# kbd.net
KiCad netlist of a schematic drawn in EAGLE
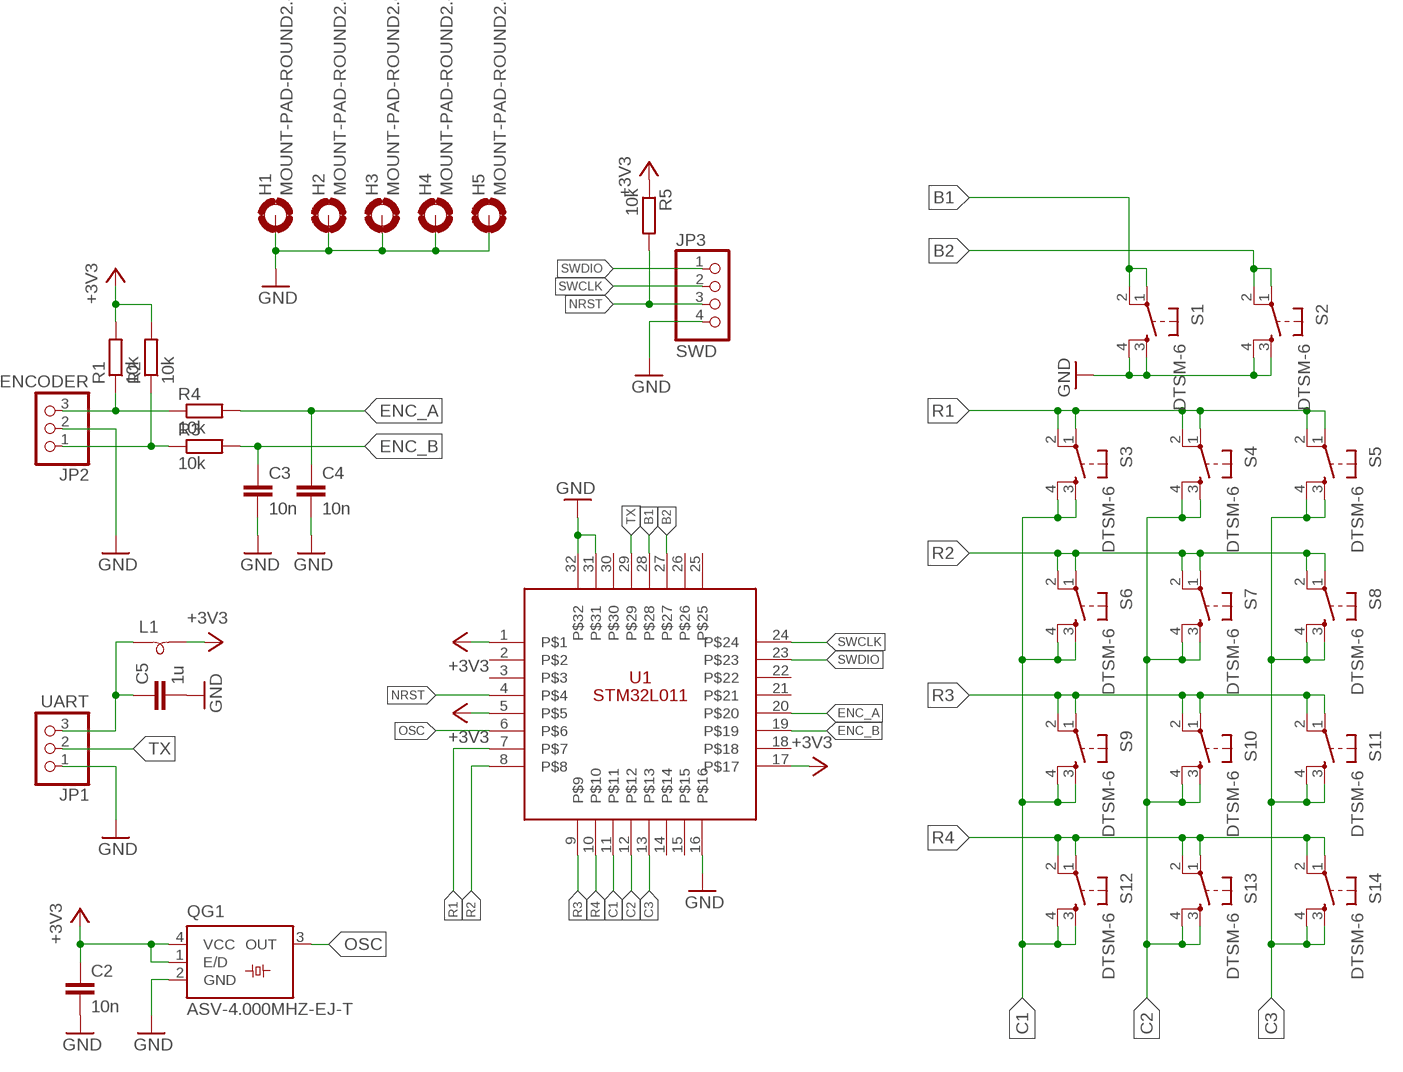
[diagram p0: schematic, sheet 1]

(export (version "E")
  (design (tool "Eeschema 10.0.6"))
  (components
    (comp (ref "C2")
      (value "10n")
      (footprint "eagle-import:C0805")
      (libsource (lib "eagle-import") (part "C-EUC0805"))
    )
    (comp (ref "C3")
      (value "10n")
      (footprint "eagle-import:C0805")
      (libsource (lib "eagle-import") (part "C-EUC0805"))
    )
    (comp (ref "C4")
      (value "10n")
      (footprint "eagle-import:C0805")
      (libsource (lib "eagle-import") (part "C-EUC0805"))
    )
    (comp (ref "C5")
      (value "1u")
      (footprint "eagle-import:C1206")
      (libsource (lib "eagle-import") (part "C-EUC1206"))
    )
    (comp (ref "H1")
      (value "MOUNT-PAD-ROUND2.8")
      (footprint "eagle-import:2,8-PAD")
      (libsource (lib "eagle-import") (part "MOUNT-PAD-ROUND2.8"))
    )
    (comp (ref "H2")
      (value "MOUNT-PAD-ROUND2.8")
      (footprint "eagle-import:2,8-PAD")
      (libsource (lib "eagle-import") (part "MOUNT-PAD-ROUND2.8"))
    )
    (comp (ref "H3")
      (value "MOUNT-PAD-ROUND2.8")
      (footprint "eagle-import:2,8-PAD")
      (libsource (lib "eagle-import") (part "MOUNT-PAD-ROUND2.8"))
    )
    (comp (ref "H4")
      (value "MOUNT-PAD-ROUND2.8")
      (footprint "eagle-import:2,8-PAD")
      (libsource (lib "eagle-import") (part "MOUNT-PAD-ROUND2.8"))
    )
    (comp (ref "H5")
      (value "MOUNT-PAD-ROUND2.8")
      (footprint "eagle-import:2,8-PAD")
      (libsource (lib "eagle-import") (part "MOUNT-PAD-ROUND2.8"))
    )
    (comp (ref "JP1")
      (value "UART")
      (footprint "eagle-import:1X03")
      (libsource (lib "eagle-import") (part "PINHD-1X3"))
    )
    (comp (ref "JP2")
      (value "ENCODER")
      (footprint "eagle-import:1X03")
      (libsource (lib "eagle-import") (part "PINHD-1X3"))
    )
    (comp (ref "JP3")
      (value "SWD")
      (footprint "eagle-import:1X04")
      (libsource (lib "eagle-import") (part "PINHD-1X4"))
    )
    (comp (ref "L1")
      (value "SM-B5")
      (footprint "eagle-import:SM-B5")
      (libsource (lib "eagle-import") (part "SM-B5"))
    )
    (comp (ref "QG1")
      (value "ASV-4.000MHZ-EJ-T")
      (footprint "eagle-import:SM77H")
      (libsource (lib "eagle-import") (part "SM77H"))
    )
    (comp (ref "R1")
      (value "10k")
      (footprint "eagle-import:R0805")
      (libsource (lib "eagle-import") (part "R-EU_R0805"))
    )
    (comp (ref "R2")
      (value "10k")
      (footprint "eagle-import:R0805")
      (libsource (lib "eagle-import") (part "R-EU_R0805"))
    )
    (comp (ref "R3")
      (value "10k")
      (footprint "eagle-import:R0805")
      (libsource (lib "eagle-import") (part "R-EU_R0805"))
    )
    (comp (ref "R4")
      (value "10k")
      (footprint "eagle-import:R0805")
      (libsource (lib "eagle-import") (part "R-EU_R0805"))
    )
    (comp (ref "R5")
      (value "10k")
      (footprint "eagle-import:R0805")
      (libsource (lib "eagle-import") (part "R-EU_R0805"))
    )
    (comp (ref "S1")
      (value "DTSM-6")
      (footprint "eagle-import:DTSM-6")
      (libsource (lib "eagle-import") (part "DTSM-6"))
    )
    (comp (ref "S2")
      (value "DTSM-6")
      (footprint "eagle-import:DTSM-6")
      (libsource (lib "eagle-import") (part "DTSM-6"))
    )
    (comp (ref "S3")
      (value "DTSM-6")
      (footprint "eagle-import:DTSM-6")
      (libsource (lib "eagle-import") (part "DTSM-6"))
    )
    (comp (ref "S4")
      (value "DTSM-6")
      (footprint "eagle-import:DTSM-6")
      (libsource (lib "eagle-import") (part "DTSM-6"))
    )
    (comp (ref "S5")
      (value "DTSM-6")
      (footprint "eagle-import:DTSM-6")
      (libsource (lib "eagle-import") (part "DTSM-6"))
    )
    (comp (ref "S6")
      (value "DTSM-6")
      (footprint "eagle-import:DTSM-6")
      (libsource (lib "eagle-import") (part "DTSM-6"))
    )
    (comp (ref "S7")
      (value "DTSM-6")
      (footprint "eagle-import:DTSM-6")
      (libsource (lib "eagle-import") (part "DTSM-6"))
    )
    (comp (ref "S8")
      (value "DTSM-6")
      (footprint "eagle-import:DTSM-6")
      (libsource (lib "eagle-import") (part "DTSM-6"))
    )
    (comp (ref "S9")
      (value "DTSM-6")
      (footprint "eagle-import:DTSM-6")
      (libsource (lib "eagle-import") (part "DTSM-6"))
    )
    (comp (ref "S10")
      (value "DTSM-6")
      (footprint "eagle-import:DTSM-6")
      (libsource (lib "eagle-import") (part "DTSM-6"))
    )
    (comp (ref "S11")
      (value "DTSM-6")
      (footprint "eagle-import:DTSM-6")
      (libsource (lib "eagle-import") (part "DTSM-6"))
    )
    (comp (ref "S12")
      (value "DTSM-6")
      (footprint "eagle-import:DTSM-6")
      (libsource (lib "eagle-import") (part "DTSM-6"))
    )
    (comp (ref "S13")
      (value "DTSM-6")
      (footprint "eagle-import:DTSM-6")
      (libsource (lib "eagle-import") (part "DTSM-6"))
    )
    (comp (ref "S14")
      (value "DTSM-6")
      (footprint "eagle-import:DTSM-6")
      (libsource (lib "eagle-import") (part "DTSM-6"))
    )
    (comp (ref "U1")
      (value "STM32L011")
      (footprint "eagle-import:LQFP32-7X7")
      (libsource (lib "eagle-import") (part "STM32L011"))
    )
  )
  (nets
    (net (code "1") (name "+3V3") (class "Default")
      (node (ref "C2") (pin "1") (pinfunction "1_1") (pintype "passive"))
      (node (ref "L1") (pin "2") (pinfunction "2_2") (pintype "passive"))
      (node (ref "QG1") (pin "1") (pinfunction "E/D_1") (pintype "input"))
      (node (ref "QG1") (pin "4") (pinfunction "VCC_4") (pintype "power_in"))
      (node (ref "R1") (pin "2") (pinfunction "2_2") (pintype "passive"))
      (node (ref "R2") (pin "2") (pinfunction "2_2") (pintype "passive"))
      (node (ref "R5") (pin "1") (pinfunction "1_1") (pintype "passive"))
      (node (ref "U1") (pin "1") (pinfunction "P$1_1") (pintype "bidirectional"))
      (node (ref "U1") (pin "17") (pinfunction "P$17_17") (pintype "bidirectional"))
      (node (ref "U1") (pin "5") (pinfunction "P$5_5") (pintype "bidirectional"))
    )
    (net (code "2") (name "B1") (class "Default")
      (node (ref "S1") (pin "1") (pinfunction "1_1") (pintype "passive"))
      (node (ref "S1") (pin "2") (pinfunction "2_2") (pintype "passive"))
      (node (ref "U1") (pin "28") (pinfunction "P$28_28") (pintype "bidirectional"))
    )
    (net (code "3") (name "B2") (class "Default")
      (node (ref "S2") (pin "1") (pinfunction "1_1") (pintype "passive"))
      (node (ref "S2") (pin "2") (pinfunction "2_2") (pintype "passive"))
      (node (ref "U1") (pin "27") (pinfunction "P$27_27") (pintype "bidirectional"))
    )
    (net (code "4") (name "C1") (class "Default")
      (node (ref "S12") (pin "3") (pinfunction "3_3") (pintype "passive"))
      (node (ref "S12") (pin "4") (pinfunction "4_4") (pintype "passive"))
      (node (ref "S3") (pin "3") (pinfunction "3_3") (pintype "passive"))
      (node (ref "S3") (pin "4") (pinfunction "4_4") (pintype "passive"))
      (node (ref "S6") (pin "3") (pinfunction "3_3") (pintype "passive"))
      (node (ref "S6") (pin "4") (pinfunction "4_4") (pintype "passive"))
      (node (ref "S9") (pin "3") (pinfunction "3_3") (pintype "passive"))
      (node (ref "S9") (pin "4") (pinfunction "4_4") (pintype "passive"))
      (node (ref "U1") (pin "11") (pinfunction "P$11_11") (pintype "bidirectional"))
    )
    (net (code "5") (name "C2") (class "Default")
      (node (ref "S10") (pin "3") (pinfunction "3_3") (pintype "passive"))
      (node (ref "S10") (pin "4") (pinfunction "4_4") (pintype "passive"))
      (node (ref "S13") (pin "3") (pinfunction "3_3") (pintype "passive"))
      (node (ref "S13") (pin "4") (pinfunction "4_4") (pintype "passive"))
      (node (ref "S4") (pin "3") (pinfunction "3_3") (pintype "passive"))
      (node (ref "S4") (pin "4") (pinfunction "4_4") (pintype "passive"))
      (node (ref "S7") (pin "3") (pinfunction "3_3") (pintype "passive"))
      (node (ref "S7") (pin "4") (pinfunction "4_4") (pintype "passive"))
      (node (ref "U1") (pin "12") (pinfunction "P$12_12") (pintype "bidirectional"))
    )
    (net (code "6") (name "C3") (class "Default")
      (node (ref "S11") (pin "3") (pinfunction "3_3") (pintype "passive"))
      (node (ref "S11") (pin "4") (pinfunction "4_4") (pintype "passive"))
      (node (ref "S14") (pin "3") (pinfunction "3_3") (pintype "passive"))
      (node (ref "S14") (pin "4") (pinfunction "4_4") (pintype "passive"))
      (node (ref "S5") (pin "3") (pinfunction "3_3") (pintype "passive"))
      (node (ref "S5") (pin "4") (pinfunction "4_4") (pintype "passive"))
      (node (ref "S8") (pin "3") (pinfunction "3_3") (pintype "passive"))
      (node (ref "S8") (pin "4") (pinfunction "4_4") (pintype "passive"))
      (node (ref "U1") (pin "13") (pinfunction "P$13_13") (pintype "bidirectional"))
    )
    (net (code "7") (name "ENC_A") (class "Default")
      (node (ref "C4") (pin "1") (pinfunction "1_1") (pintype "passive"))
      (node (ref "R4") (pin "2") (pinfunction "2_2") (pintype "passive"))
      (node (ref "U1") (pin "20") (pinfunction "P$20_20") (pintype "bidirectional"))
    )
    (net (code "8") (name "ENC_B") (class "Default")
      (node (ref "C3") (pin "1") (pinfunction "1_1") (pintype "passive"))
      (node (ref "R3") (pin "2") (pinfunction "2_2") (pintype "passive"))
      (node (ref "U1") (pin "19") (pinfunction "P$19_19") (pintype "bidirectional"))
    )
    (net (code "9") (name "GND") (class "Default")
      (node (ref "C2") (pin "2") (pinfunction "2_2") (pintype "passive"))
      (node (ref "C3") (pin "2") (pinfunction "2_2") (pintype "passive"))
      (node (ref "C4") (pin "2") (pinfunction "2_2") (pintype "passive"))
      (node (ref "C5") (pin "2") (pinfunction "2_2") (pintype "passive"))
      (node (ref "H1") (pin "B2,8") (pinfunction "MOUNT_B2,8") (pintype "passive"))
      (node (ref "H2") (pin "B2,8") (pinfunction "MOUNT_B2,8") (pintype "passive"))
      (node (ref "H3") (pin "B2,8") (pinfunction "MOUNT_B2,8") (pintype "passive"))
      (node (ref "H4") (pin "B2,8") (pinfunction "MOUNT_B2,8") (pintype "passive"))
      (node (ref "H5") (pin "B2,8") (pinfunction "MOUNT_B2,8") (pintype "passive"))
      (node (ref "JP1") (pin "1") (pinfunction "1_1") (pintype "passive"))
      (node (ref "JP2") (pin "2") (pinfunction "2_2") (pintype "passive"))
      (node (ref "JP3") (pin "4") (pinfunction "4_4") (pintype "passive"))
      (node (ref "QG1") (pin "2") (pinfunction "GND_2") (pintype "power_in"))
      (node (ref "S1") (pin "3") (pinfunction "3_3") (pintype "passive"))
      (node (ref "S1") (pin "4") (pinfunction "4_4") (pintype "passive"))
      (node (ref "S2") (pin "3") (pinfunction "3_3") (pintype "passive"))
      (node (ref "S2") (pin "4") (pinfunction "4_4") (pintype "passive"))
      (node (ref "U1") (pin "16") (pinfunction "P$16_16") (pintype "bidirectional"))
      (node (ref "U1") (pin "31") (pinfunction "P$31_31") (pintype "bidirectional"))
      (node (ref "U1") (pin "32") (pinfunction "P$32_32") (pintype "bidirectional"))
    )
    (net (code "10") (name "NRST") (class "Default")
      (node (ref "JP3") (pin "3") (pinfunction "3_3") (pintype "passive"))
      (node (ref "R5") (pin "2") (pinfunction "2_2") (pintype "passive"))
      (node (ref "U1") (pin "4") (pinfunction "P$4_4") (pintype "bidirectional"))
    )
    (net (code "11") (name "Net-(C5-Pad1)") (class "Default")
      (node (ref "C5") (pin "1") (pinfunction "1_1") (pintype "passive"))
      (node (ref "JP1") (pin "3") (pinfunction "3_3") (pintype "passive"))
      (node (ref "L1") (pin "1") (pinfunction "1_1") (pintype "passive"))
    )
    (net (code "12") (name "Net-(JP2-Pad1)") (class "Default")
      (node (ref "JP2") (pin "1") (pinfunction "1_1") (pintype "passive"))
      (node (ref "R2") (pin "1") (pinfunction "1_1") (pintype "passive"))
      (node (ref "R3") (pin "1") (pinfunction "1_1") (pintype "passive"))
    )
    (net (code "13") (name "Net-(JP2-Pad3)") (class "Default")
      (node (ref "JP2") (pin "3") (pinfunction "3_3") (pintype "passive"))
      (node (ref "R1") (pin "1") (pinfunction "1_1") (pintype "passive"))
      (node (ref "R4") (pin "1") (pinfunction "1_1") (pintype "passive"))
    )
    (net (code "14") (name "OSC") (class "Default")
      (node (ref "QG1") (pin "3") (pinfunction "OUT_3") (pintype "output"))
      (node (ref "U1") (pin "6") (pinfunction "P$6_6") (pintype "bidirectional"))
    )
    (net (code "15") (name "R1") (class "Default")
      (node (ref "S3") (pin "1") (pinfunction "1_1") (pintype "passive"))
      (node (ref "S3") (pin "2") (pinfunction "2_2") (pintype "passive"))
      (node (ref "S4") (pin "1") (pinfunction "1_1") (pintype "passive"))
      (node (ref "S4") (pin "2") (pinfunction "2_2") (pintype "passive"))
      (node (ref "S5") (pin "1") (pinfunction "1_1") (pintype "passive"))
      (node (ref "S5") (pin "2") (pinfunction "2_2") (pintype "passive"))
      (node (ref "U1") (pin "7") (pinfunction "P$7_7") (pintype "bidirectional"))
    )
    (net (code "16") (name "R2") (class "Default")
      (node (ref "S6") (pin "1") (pinfunction "1_1") (pintype "passive"))
      (node (ref "S6") (pin "2") (pinfunction "2_2") (pintype "passive"))
      (node (ref "S7") (pin "1") (pinfunction "1_1") (pintype "passive"))
      (node (ref "S7") (pin "2") (pinfunction "2_2") (pintype "passive"))
      (node (ref "S8") (pin "1") (pinfunction "1_1") (pintype "passive"))
      (node (ref "S8") (pin "2") (pinfunction "2_2") (pintype "passive"))
      (node (ref "U1") (pin "8") (pinfunction "P$8_8") (pintype "bidirectional"))
    )
    (net (code "17") (name "R3") (class "Default")
      (node (ref "S10") (pin "1") (pinfunction "1_1") (pintype "passive"))
      (node (ref "S10") (pin "2") (pinfunction "2_2") (pintype "passive"))
      (node (ref "S11") (pin "1") (pinfunction "1_1") (pintype "passive"))
      (node (ref "S11") (pin "2") (pinfunction "2_2") (pintype "passive"))
      (node (ref "S9") (pin "1") (pinfunction "1_1") (pintype "passive"))
      (node (ref "S9") (pin "2") (pinfunction "2_2") (pintype "passive"))
      (node (ref "U1") (pin "9") (pinfunction "P$9_9") (pintype "bidirectional"))
    )
    (net (code "18") (name "R4") (class "Default")
      (node (ref "S12") (pin "1") (pinfunction "1_1") (pintype "passive"))
      (node (ref "S12") (pin "2") (pinfunction "2_2") (pintype "passive"))
      (node (ref "S13") (pin "1") (pinfunction "1_1") (pintype "passive"))
      (node (ref "S13") (pin "2") (pinfunction "2_2") (pintype "passive"))
      (node (ref "S14") (pin "1") (pinfunction "1_1") (pintype "passive"))
      (node (ref "S14") (pin "2") (pinfunction "2_2") (pintype "passive"))
      (node (ref "U1") (pin "10") (pinfunction "P$10_10") (pintype "bidirectional"))
    )
    (net (code "19") (name "SWCLK") (class "Default")
      (node (ref "JP3") (pin "2") (pinfunction "2_2") (pintype "passive"))
      (node (ref "U1") (pin "24") (pinfunction "P$24_24") (pintype "bidirectional"))
    )
    (net (code "20") (name "SWDIO") (class "Default")
      (node (ref "JP3") (pin "1") (pinfunction "1_1") (pintype "passive"))
      (node (ref "U1") (pin "23") (pinfunction "P$23_23") (pintype "bidirectional"))
    )
    (net (code "21") (name "TX") (class "Default")
      (node (ref "JP1") (pin "2") (pinfunction "2_2") (pintype "passive"))
      (node (ref "U1") (pin "29") (pinfunction "P$29_29") (pintype "bidirectional"))
    )
    (net (code "22") (name "unconnected-(U1-P$2-Pad2)") (class "Default")
      (node (ref "U1") (pin "2") (pinfunction "P$2_2") (pintype "bidirectional"))
    )
    (net (code "23") (name "unconnected-(U1-P$3-Pad3)") (class "Default")
      (node (ref "U1") (pin "3") (pinfunction "P$3_3") (pintype "bidirectional"))
    )
    (net (code "24") (name "unconnected-(U1-P$14-Pad14)") (class "Default")
      (node (ref "U1") (pin "14") (pinfunction "P$14_14") (pintype "bidirectional"))
    )
    (net (code "25") (name "unconnected-(U1-P$15-Pad15)") (class "Default")
      (node (ref "U1") (pin "15") (pinfunction "P$15_15") (pintype "bidirectional"))
    )
    (net (code "26") (name "unconnected-(U1-P$18-Pad18)") (class "Default")
      (node (ref "U1") (pin "18") (pinfunction "P$18_18") (pintype "bidirectional"))
    )
    (net (code "27") (name "unconnected-(U1-P$21-Pad21)") (class "Default")
      (node (ref "U1") (pin "21") (pinfunction "P$21_21") (pintype "bidirectional"))
    )
    (net (code "28") (name "unconnected-(U1-P$22-Pad22)") (class "Default")
      (node (ref "U1") (pin "22") (pinfunction "P$22_22") (pintype "bidirectional"))
    )
    (net (code "29") (name "unconnected-(U1-P$25-Pad25)") (class "Default")
      (node (ref "U1") (pin "25") (pinfunction "P$25_25") (pintype "bidirectional"))
    )
    (net (code "30") (name "unconnected-(U1-P$26-Pad26)") (class "Default")
      (node (ref "U1") (pin "26") (pinfunction "P$26_26") (pintype "bidirectional"))
    )
    (net (code "31") (name "unconnected-(U1-P$30-Pad30)") (class "Default")
      (node (ref "U1") (pin "30") (pinfunction "P$30_30") (pintype "bidirectional"))
    )
  )
)
